# PiModulos_-_Rams_Head.net
KiCad netlist of a schematic drawn in Altium Designer
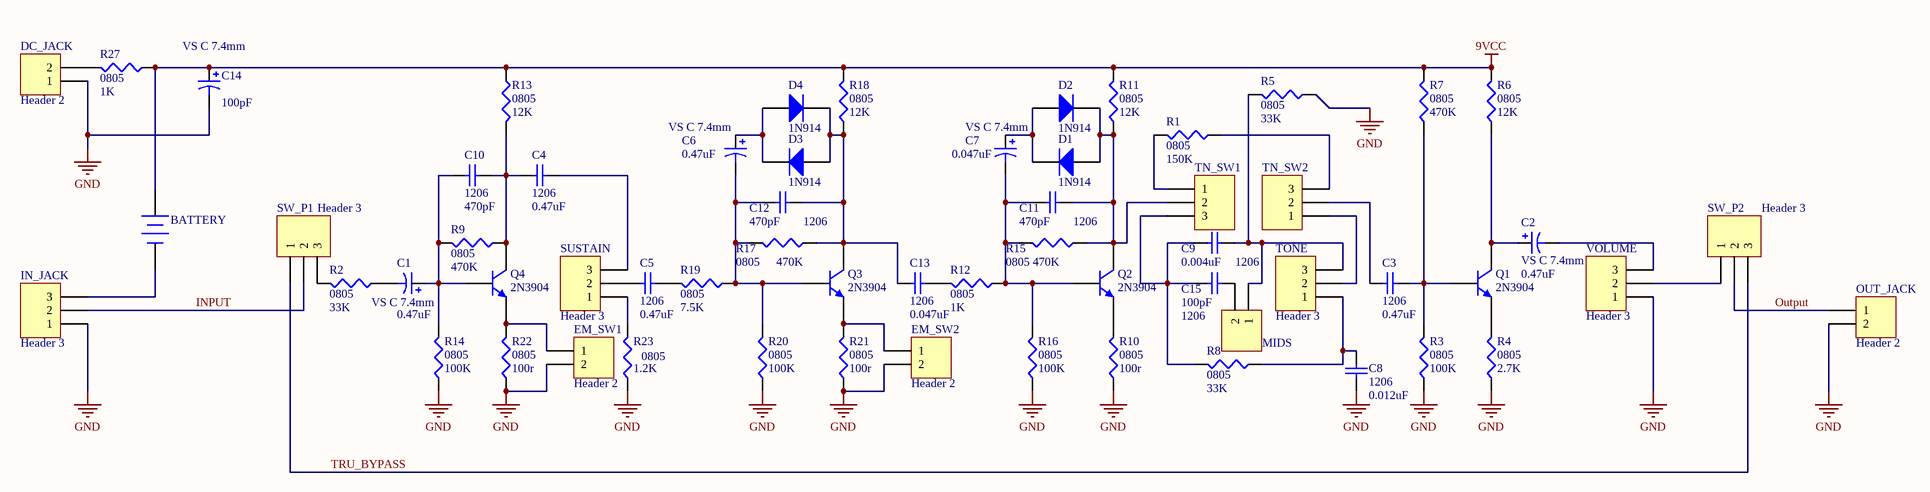
[diagram p0: PiModulos - Rams Head.SchDoc]

(export (version "E")
  (design (tool "Eeschema 10.0.6"))
  (components
    (comp (ref "BATTERY")
      (value "Battery")
      (footprint "BAT-2")
      (description "Multicell Battery")
      (fields (field (name "PUBLISHER") "Altium Limited"))
      (libsource (lib "Miscellaneous Devices") (part "Battery"))
    )
    (comp (ref "C1")
      (value "VS C 7.4mm")
      (footprint "Panasonic VS C")
      (description "Polarized Capacitor (Radial)")
      (fields (field (name "ALTIUM_VALUE") "0.47uF") (field (name "PUBLISHER") "Altium Limited"))
      (libsource (lib "Miscellaneous Devices") (part "Cap Pol1"))
    )
    (comp (ref "C2")
      (value "VS C 7.4mm")
      (footprint "Panasonic VS C")
      (description "Polarized Capacitor (Radial)")
      (fields (field (name "ALTIUM_VALUE") "0.47uF") (field (name "PUBLISHER") "Altium Limited"))
      (libsource (lib "Miscellaneous Devices") (part "Cap Pol1"))
    )
    (comp (ref "C3")
      (value "1206")
      (footprint "C1206")
      (description "Capacitor (Semiconductor SIM Model)")
      (fields (field (name "ALTIUM_VALUE") "0.47uF") (field (name "PUBLISHER") "Altium Limited"))
      (libsource (lib "Miscellaneous Devices") (part "Cap Semi"))
    )
    (comp (ref "C4")
      (value "1206")
      (footprint "C1206")
      (description "Capacitor (Semiconductor SIM Model)")
      (fields (field (name "ALTIUM_VALUE") "0.47uF") (field (name "PUBLISHER") "Altium Limited"))
      (libsource (lib "Miscellaneous Devices") (part "Cap Semi"))
    )
    (comp (ref "C5")
      (value "1206")
      (footprint "C1206")
      (description "Capacitor (Semiconductor SIM Model)")
      (fields (field (name "ALTIUM_VALUE") "0.47uF") (field (name "PUBLISHER") "Altium Limited"))
      (libsource (lib "Miscellaneous Devices") (part "Cap Semi"))
    )
    (comp (ref "C6")
      (value "VS C 7.4mm")
      (footprint "Panasonic VS C")
      (description "Polarized Capacitor (Radial)")
      (fields (field (name "ALTIUM_VALUE") "0.47uF") (field (name "PUBLISHER") "Altium Limited"))
      (libsource (lib "Miscellaneous Devices") (part "Cap Pol1"))
    )
    (comp (ref "C7")
      (value "VS C 7.4mm")
      (footprint "Panasonic VS C")
      (description "Polarized Capacitor (Radial)")
      (fields (field (name "ALTIUM_VALUE") "0.047uF") (field (name "PUBLISHER") "Altium Limited"))
      (libsource (lib "Miscellaneous Devices") (part "Cap Pol1"))
    )
    (comp (ref "C8")
      (value "1206")
      (footprint "C1206")
      (description "Capacitor (Semiconductor SIM Model)")
      (fields (field (name "ALTIUM_VALUE") "0.012uF") (field (name "PUBLISHER") "Altium Limited"))
      (libsource (lib "Miscellaneous Devices") (part "Cap Semi"))
    )
    (comp (ref "C9")
      (value "1206")
      (footprint "C1206")
      (description "Capacitor (Semiconductor SIM Model)")
      (fields (field (name "ALTIUM_VALUE") "0.004uF") (field (name "PUBLISHER") "Altium Limited"))
      (libsource (lib "Miscellaneous Devices") (part "Cap Semi"))
    )
    (comp (ref "C10")
      (value "1206")
      (footprint "C1206")
      (description "Capacitor (Semiconductor SIM Model)")
      (fields (field (name "ALTIUM_VALUE") "470pF") (field (name "PUBLISHER") "Altium Limited"))
      (libsource (lib "Miscellaneous Devices") (part "Cap Semi"))
    )
    (comp (ref "C11")
      (value "1206")
      (footprint "C1206")
      (description "Capacitor (Semiconductor SIM Model)")
      (fields (field (name "ALTIUM_VALUE") "470pF") (field (name "PUBLISHER") "Altium Limited"))
      (libsource (lib "Miscellaneous Devices") (part "Cap Semi"))
    )
    (comp (ref "C12")
      (value "1206")
      (footprint "C1206")
      (description "Capacitor (Semiconductor SIM Model)")
      (fields (field (name "ALTIUM_VALUE") "470pF") (field (name "PUBLISHER") "Altium Limited"))
      (libsource (lib "Miscellaneous Devices") (part "Cap Semi"))
    )
    (comp (ref "C13")
      (value "1206")
      (footprint "C1206")
      (description "Capacitor (Semiconductor SIM Model)")
      (fields (field (name "ALTIUM_VALUE") "0.047uF") (field (name "PUBLISHER") "Altium Limited"))
      (libsource (lib "Miscellaneous Devices") (part "Cap Semi"))
    )
    (comp (ref "C14")
      (value "VS C 7.4mm")
      (footprint "Panasonic VS C")
      (description "Polarized Capacitor (Radial)")
      (fields (field (name "ALTIUM_VALUE") "100pF") (field (name "PUBLISHER") "Altium Limited"))
      (libsource (lib "Miscellaneous Devices") (part "Cap Pol1"))
    )
    (comp (ref "C15")
      (value "1206")
      (footprint "C1206")
      (description "Capacitor (Semiconductor SIM Model)")
      (fields (field (name "ALTIUM_VALUE") "100pF") (field (name "PUBLISHER") "Altium Limited"))
      (libsource (lib "Miscellaneous Devices") (part "Cap Semi"))
    )
    (comp (ref "D1")
      (value "1N914")
      (footprint "DO-35")
      (description "High Conductance Fast Diode")
      (fields (field (name "PUBLISHER") "Altium Limited"))
      (libsource (lib "Miscellaneous Devices") (part "Diode 1N914"))
    )
    (comp (ref "D2")
      (value "1N914")
      (footprint "DO-35")
      (description "High Conductance Fast Diode")
      (fields (field (name "PUBLISHER") "Altium Limited"))
      (libsource (lib "Miscellaneous Devices") (part "Diode 1N914"))
    )
    (comp (ref "D3")
      (value "1N914")
      (footprint "DO-35")
      (description "High Conductance Fast Diode")
      (fields (field (name "PUBLISHER") "Altium Limited"))
      (libsource (lib "Miscellaneous Devices") (part "Diode 1N914"))
    )
    (comp (ref "D4")
      (value "1N914")
      (footprint "DO-35")
      (description "High Conductance Fast Diode")
      (fields (field (name "PUBLISHER") "Altium Limited"))
      (libsource (lib "Miscellaneous Devices") (part "Diode 1N914"))
    )
    (comp (ref "DC_JACK")
      (value "Header 2")
      (footprint "HDR1X2")
      (description "Header, 2-Pin")
      (fields (field (name "PUBLISHER") "Altium Limited"))
      (libsource (lib "") (part "Header 2_2"))
    )
    (comp (ref "EM_SW1")
      (value "Header 2")
      (footprint "HDR1X2")
      (description "Header, 2-Pin")
      (fields (field (name "PUBLISHER") "Altium Limited"))
      (libsource (lib "Miscellaneous Connectors") (part "Header 2"))
    )
    (comp (ref "EM_SW2")
      (value "Header 2")
      (footprint "HDR1X2")
      (description "Header, 2-Pin")
      (fields (field (name "PUBLISHER") "Altium Limited"))
      (libsource (lib "Miscellaneous Connectors") (part "Header 2"))
    )
    (comp (ref "IN_JACK")
      (value "Header 3")
      (footprint "HDR1X3")
      (description "Header, 3-Pin")
      (fields (field (name "PUBLISHER") "Altium Limited"))
      (libsource (lib "Miscellaneous Connectors") (part "Header 3"))
    )
    (comp (ref "MIDS")
      (value "Header 2")
      (footprint "HDR1X2")
      (description "Header, 2-Pin")
      (fields (field (name "PUBLISHER") "Altium Limited"))
      (libsource (lib "") (part "Header 2_1"))
    )
    (comp (ref "OUT_JACK")
      (value "Header 2")
      (footprint "HDR1X2")
      (description "Header, 2-Pin")
      (fields (field (name "PUBLISHER") "Altium Limited"))
      (libsource (lib "Miscellaneous Connectors") (part "Header 2"))
    )
    (comp (ref "Q1")
      (value "2N3904")
      (footprint "TO-92A")
      (description "NPN General Purpose Amplifier")
      (fields (field (name "PUBLISHER") "Altium Limited"))
      (libsource (lib "Miscellaneous Devices") (part "2N3904"))
    )
    (comp (ref "Q2")
      (value "2N3904")
      (footprint "TO-92A")
      (description "NPN General Purpose Amplifier")
      (fields (field (name "PUBLISHER") "Altium Limited"))
      (libsource (lib "Miscellaneous Devices") (part "2N3904"))
    )
    (comp (ref "Q3")
      (value "2N3904")
      (footprint "TO-92A")
      (description "NPN General Purpose Amplifier")
      (fields (field (name "PUBLISHER") "Altium Limited"))
      (libsource (lib "Miscellaneous Devices") (part "2N3904"))
    )
    (comp (ref "Q4")
      (value "2N3904")
      (footprint "TO-92A")
      (description "NPN General Purpose Amplifier")
      (fields (field (name "PUBLISHER") "Altium Limited"))
      (libsource (lib "Miscellaneous Devices") (part "2N3904"))
    )
    (comp (ref "R1")
      (value "0805")
      (footprint "SM 0805 - gap trimmed")
      (description "Resistor")
      (fields (field (name "ALTIUM_VALUE") "150K") (field (name "PUBLISHER") "Altium Limited"))
      (libsource (lib "Miscellaneous Devices") (part "Res3"))
    )
    (comp (ref "R2")
      (value "0805")
      (footprint "SM 0805 - gap trimmed")
      (description "Resistor")
      (fields (field (name "ALTIUM_VALUE") "33K") (field (name "PUBLISHER") "Altium Limited"))
      (libsource (lib "Miscellaneous Devices") (part "Res3"))
    )
    (comp (ref "R3")
      (value "0805")
      (footprint "SM 0805 - gap trimmed")
      (description "Resistor")
      (fields (field (name "ALTIUM_VALUE") "100K") (field (name "PUBLISHER") "Altium Limited"))
      (libsource (lib "Miscellaneous Devices") (part "Res3"))
    )
    (comp (ref "R4")
      (value "0805")
      (footprint "SM 0805 - gap trimmed")
      (description "Resistor")
      (fields (field (name "ALTIUM_VALUE") "2.7K") (field (name "PUBLISHER") "Altium Limited"))
      (libsource (lib "Miscellaneous Devices") (part "Res3"))
    )
    (comp (ref "R5")
      (value "0805")
      (footprint "SM 0805 - gap trimmed")
      (description "Resistor")
      (fields (field (name "ALTIUM_VALUE") "33K") (field (name "PUBLISHER") "Altium Limited"))
      (libsource (lib "Miscellaneous Devices") (part "Res3"))
    )
    (comp (ref "R6")
      (value "0805")
      (footprint "SM 0805 - gap trimmed")
      (description "Resistor")
      (fields (field (name "ALTIUM_VALUE") "12K") (field (name "PUBLISHER") "Altium Limited"))
      (libsource (lib "Miscellaneous Devices") (part "Res3"))
    )
    (comp (ref "R7")
      (value "0805")
      (footprint "SM 0805 - gap trimmed")
      (description "Resistor")
      (fields (field (name "ALTIUM_VALUE") "470K") (field (name "PUBLISHER") "Altium Limited"))
      (libsource (lib "Miscellaneous Devices") (part "Res3"))
    )
    (comp (ref "R8")
      (value "0805")
      (footprint "SM 0805 - gap trimmed")
      (description "Resistor")
      (fields (field (name "ALTIUM_VALUE") "33K") (field (name "PUBLISHER") "Altium Limited"))
      (libsource (lib "Miscellaneous Devices") (part "Res3"))
    )
    (comp (ref "R9")
      (value "0805")
      (footprint "SM 0805 - gap trimmed")
      (description "Resistor")
      (fields (field (name "ALTIUM_VALUE") "470K") (field (name "PUBLISHER") "Altium Limited"))
      (libsource (lib "Miscellaneous Devices") (part "Res3"))
    )
    (comp (ref "R10")
      (value "0805")
      (footprint "SM 0805 - gap trimmed")
      (description "Resistor")
      (fields (field (name "ALTIUM_VALUE") "100r") (field (name "PUBLISHER") "Altium Limited"))
      (libsource (lib "Miscellaneous Devices") (part "Res3"))
    )
    (comp (ref "R11")
      (value "0805")
      (footprint "SM 0805 - gap trimmed")
      (description "Resistor")
      (fields (field (name "ALTIUM_VALUE") "12K") (field (name "PUBLISHER") "Altium Limited"))
      (libsource (lib "Miscellaneous Devices") (part "Res3"))
    )
    (comp (ref "R12")
      (value "0805")
      (footprint "SM 0805 - gap trimmed")
      (description "Resistor")
      (fields (field (name "ALTIUM_VALUE") "1K") (field (name "PUBLISHER") "Altium Limited"))
      (libsource (lib "Miscellaneous Devices") (part "Res3"))
    )
    (comp (ref "R13")
      (value "0805")
      (footprint "SM 0805 - gap trimmed")
      (description "Resistor")
      (fields (field (name "ALTIUM_VALUE") "12K") (field (name "PUBLISHER") "Altium Limited"))
      (libsource (lib "Miscellaneous Devices") (part "Res3"))
    )
    (comp (ref "R14")
      (value "0805")
      (footprint "SM 0805 - gap trimmed")
      (description "Resistor")
      (fields (field (name "ALTIUM_VALUE") "100K") (field (name "PUBLISHER") "Altium Limited"))
      (libsource (lib "Miscellaneous Devices") (part "Res3"))
    )
    (comp (ref "R15")
      (value "0805")
      (footprint "SM 0805 - gap trimmed")
      (description "Resistor")
      (fields (field (name "ALTIUM_VALUE") "470K") (field (name "PUBLISHER") "Altium Limited"))
      (libsource (lib "Miscellaneous Devices") (part "Res3"))
    )
    (comp (ref "R16")
      (value "0805")
      (footprint "SM 0805 - gap trimmed")
      (description "Resistor")
      (fields (field (name "ALTIUM_VALUE") "100K") (field (name "PUBLISHER") "Altium Limited"))
      (libsource (lib "Miscellaneous Devices") (part "Res3"))
    )
    (comp (ref "R17")
      (value "0805")
      (footprint "SM 0805 - gap trimmed")
      (description "Resistor")
      (fields (field (name "ALTIUM_VALUE") "470K") (field (name "PUBLISHER") "Altium Limited"))
      (libsource (lib "Miscellaneous Devices") (part "Res3"))
    )
    (comp (ref "R18")
      (value "0805")
      (footprint "SM 0805 - gap trimmed")
      (description "Resistor")
      (fields (field (name "ALTIUM_VALUE") "12K") (field (name "PUBLISHER") "Altium Limited"))
      (libsource (lib "Miscellaneous Devices") (part "Res3"))
    )
    (comp (ref "R19")
      (value "0805")
      (footprint "SM 0805 - gap trimmed")
      (description "Resistor")
      (fields (field (name "ALTIUM_VALUE") "7.5K") (field (name "PUBLISHER") "Altium Limited"))
      (libsource (lib "Miscellaneous Devices") (part "Res3"))
    )
    (comp (ref "R20")
      (value "0805")
      (footprint "SM 0805 - gap trimmed")
      (description "Resistor")
      (fields (field (name "ALTIUM_VALUE") "100K") (field (name "PUBLISHER") "Altium Limited"))
      (libsource (lib "Miscellaneous Devices") (part "Res3"))
    )
    (comp (ref "R21")
      (value "0805")
      (footprint "SM 0805 - gap trimmed")
      (description "Resistor")
      (fields (field (name "ALTIUM_VALUE") "100r") (field (name "PUBLISHER") "Altium Limited"))
      (libsource (lib "Miscellaneous Devices") (part "Res3"))
    )
    (comp (ref "R22")
      (value "0805")
      (footprint "SM 0805 - gap trimmed")
      (description "Resistor")
      (fields (field (name "ALTIUM_VALUE") "100r") (field (name "PUBLISHER") "Altium Limited"))
      (libsource (lib "Miscellaneous Devices") (part "Res3"))
    )
    (comp (ref "R23")
      (value "0805")
      (footprint "SM 0805 - gap trimmed")
      (description "Resistor")
      (fields (field (name "ALTIUM_VALUE") "1.2K") (field (name "PUBLISHER") "Altium Limited"))
      (libsource (lib "Miscellaneous Devices") (part "Res3"))
    )
    (comp (ref "R27")
      (value "0805")
      (footprint "SM 0805 - gap trimmed")
      (description "Resistor")
      (fields (field (name "ALTIUM_VALUE") "1K") (field (name "PUBLISHER") "Altium Limited"))
      (libsource (lib "Miscellaneous Devices") (part "Res3"))
    )
    (comp (ref "SUSTAIN")
      (value "Header 3")
      (footprint "HDR1X3")
      (description "Header, 3-Pin")
      (fields (field (name "PUBLISHER") "Altium Limited"))
      (libsource (lib "Miscellaneous Connectors") (part "Header 3"))
    )
    (comp (ref "SW_P1")
      (value "Header 3")
      (footprint "HDR1X3")
      (description "Header, 3-Pin")
      (fields (field (name "PUBLISHER") "Altium Limited"))
      (libsource (lib "") (part "Header 3_1"))
    )
    (comp (ref "SW_P2")
      (value "Header 3")
      (footprint "HDR1X3")
      (description "Header, 3-Pin")
      (fields (field (name "PUBLISHER") "Altium Limited"))
      (libsource (lib "") (part "Header 3_1"))
    )
    (comp (ref "TN_SW1")
      (value "Header 3")
      (footprint "HDR1X3")
      (description "Header, 3-Pin")
      (fields (field (name "PUBLISHER") "Altium Limited"))
      (libsource (lib "") (part "Header 3_2"))
    )
    (comp (ref "TN_SW2")
      (value "Header 3")
      (footprint "HDR1X3")
      (description "Header, 3-Pin")
      (fields (field (name "PUBLISHER") "Altium Limited"))
      (libsource (lib "Miscellaneous Connectors") (part "Header 3"))
    )
    (comp (ref "TONE")
      (value "Header 3")
      (footprint "HDR1X3")
      (description "Header, 3-Pin")
      (fields (field (name "PUBLISHER") "Altium Limited"))
      (libsource (lib "Miscellaneous Connectors") (part "Header 3"))
    )
    (comp (ref "VOLUME")
      (value "Header 3")
      (footprint "HDR1X3")
      (description "Header, 3-Pin")
      (fields (field (name "PUBLISHER") "Altium Limited"))
      (libsource (lib "Miscellaneous Connectors") (part "Header 3"))
    )
  )
  (nets
    (net (code "1") (name "/INPUT") (class "Default")
      (node (ref "IN_JACK") (pin "2") (pinfunction "2_2") (pintype "passive"))
      (node (ref "SW_P1") (pin "2") (pinfunction "2_2") (pintype "passive"))
    )
    (net (code "2") (name "/Output") (class "Default")
      (node (ref "OUT_JACK") (pin "1") (pinfunction "1_1") (pintype "passive"))
      (node (ref "SW_P2") (pin "2") (pinfunction "2_2") (pintype "passive"))
    )
    (net (code "3") (name "/TRU_BYPASS") (class "Default")
      (node (ref "SW_P1") (pin "1") (pinfunction "1_1") (pintype "passive"))
      (node (ref "SW_P2") (pin "3") (pinfunction "3_3") (pintype "passive"))
    )
    (net (code "4") (name "9VCC") (class "Default")
      (node (ref "BATTERY") (pin "1") (pinfunction "+_1") (pintype "passive"))
      (node (ref "C14") (pin "1") (pinfunction "1_1") (pintype "passive"))
      (node (ref "R11") (pin "2") (pinfunction "2_2") (pintype "passive"))
      (node (ref "R13") (pin "1") (pinfunction "1_1") (pintype "passive"))
      (node (ref "R18") (pin "2") (pinfunction "2_2") (pintype "passive"))
      (node (ref "R27") (pin "1") (pinfunction "1_1") (pintype "passive"))
      (node (ref "R6") (pin "2") (pinfunction "2_2") (pintype "passive"))
      (node (ref "R7") (pin "2") (pinfunction "2_2") (pintype "passive"))
    )
    (net (code "5") (name "GND") (class "Default")
      (node (ref "C14") (pin "2") (pinfunction "2_2") (pintype "passive"))
      (node (ref "C8") (pin "1") (pinfunction "1_1") (pintype "passive"))
      (node (ref "DC_JACK") (pin "1") (pinfunction "1_1") (pintype "passive"))
      (node (ref "EM_SW1") (pin "2") (pinfunction "2_2") (pintype "passive"))
      (node (ref "EM_SW2") (pin "2") (pinfunction "2_2") (pintype "passive"))
      (node (ref "IN_JACK") (pin "1") (pinfunction "1_1") (pintype "passive"))
      (node (ref "OUT_JACK") (pin "2") (pinfunction "2_2") (pintype "passive"))
      (node (ref "R10") (pin "1") (pinfunction "1_1") (pintype "passive"))
      (node (ref "R14") (pin "1") (pinfunction "1_1") (pintype "passive"))
      (node (ref "R16") (pin "1") (pinfunction "1_1") (pintype "passive"))
      (node (ref "R20") (pin "1") (pinfunction "1_1") (pintype "passive"))
      (node (ref "R21") (pin "1") (pinfunction "1_1") (pintype "passive"))
      (node (ref "R22") (pin "1") (pinfunction "1_1") (pintype "passive"))
      (node (ref "R23") (pin "1") (pinfunction "1_1") (pintype "passive"))
      (node (ref "R3") (pin "1") (pinfunction "1_1") (pintype "passive"))
      (node (ref "R4") (pin "1") (pinfunction "1_1") (pintype "passive"))
      (node (ref "R5") (pin "1") (pinfunction "1_1") (pintype "passive"))
      (node (ref "VOLUME") (pin "1") (pinfunction "1_1") (pintype "passive"))
    )
    (net (code "6") (name "Net-(BATTERY--)") (class "Default")
      (node (ref "BATTERY") (pin "2") (pinfunction "-_2") (pintype "passive"))
      (node (ref "IN_JACK") (pin "3") (pinfunction "3_3") (pintype "passive"))
    )
    (net (code "7") (name "Net-(C1-Pad2)") (class "Default")
      (node (ref "C1") (pin "2") (pinfunction "2_2") (pintype "passive"))
      (node (ref "R2") (pin "1") (pinfunction "1_1") (pintype "passive"))
    )
    (net (code "8") (name "Net-(C2-Pad2)") (class "Default")
      (node (ref "C2") (pin "2") (pinfunction "2_2") (pintype "passive"))
      (node (ref "VOLUME") (pin "3") (pinfunction "3_3") (pintype "passive"))
    )
    (net (code "9") (name "Net-(C3-Pad1)") (class "Default")
      (node (ref "C3") (pin "1") (pinfunction "1_1") (pintype "passive"))
      (node (ref "TN_SW2") (pin "2") (pinfunction "2_2") (pintype "passive"))
    )
    (net (code "10") (name "Net-(C4-Pad2)") (class "Default")
      (node (ref "C4") (pin "2") (pinfunction "2_2") (pintype "passive"))
      (node (ref "SUSTAIN") (pin "3") (pinfunction "3_3") (pintype "passive"))
    )
    (net (code "11") (name "Net-(C5-Pad1)") (class "Default")
      (node (ref "C5") (pin "1") (pinfunction "1_1") (pintype "passive"))
      (node (ref "SUSTAIN") (pin "2") (pinfunction "2_2") (pintype "passive"))
    )
    (net (code "12") (name "Net-(C5-Pad2)") (class "Default")
      (node (ref "C5") (pin "2") (pinfunction "2_2") (pintype "passive"))
      (node (ref "R19") (pin "2") (pinfunction "2_2") (pintype "passive"))
    )
    (net (code "13") (name "Net-(C8-Pad2)") (class "Default")
      (node (ref "C8") (pin "2") (pinfunction "2_2") (pintype "passive"))
      (node (ref "R8") (pin "1") (pinfunction "1_1") (pintype "passive"))
      (node (ref "TONE") (pin "1") (pinfunction "1_1") (pintype "passive"))
    )
    (net (code "14") (name "Net-(C9-Pad2)") (class "Default")
      (node (ref "C9") (pin "2") (pinfunction "2_2") (pintype "passive"))
      (node (ref "MIDS") (pin "1") (pinfunction "1_1") (pintype "passive"))
      (node (ref "R5") (pin "2") (pinfunction "2_2") (pintype "passive"))
      (node (ref "TONE") (pin "3") (pinfunction "3_3") (pintype "passive"))
    )
    (net (code "15") (name "Net-(C13-Pad2)") (class "Default")
      (node (ref "C13") (pin "2") (pinfunction "2_2") (pintype "passive"))
      (node (ref "R12") (pin "2") (pinfunction "2_2") (pintype "passive"))
    )
    (net (code "16") (name "Net-(C15-Pad1)") (class "Default")
      (node (ref "C15") (pin "1") (pinfunction "1_1") (pintype "passive"))
      (node (ref "C9") (pin "1") (pinfunction "1_1") (pintype "passive"))
      (node (ref "R8") (pin "2") (pinfunction "2_2") (pintype "passive"))
      (node (ref "TN_SW1") (pin "3") (pinfunction "3_3") (pintype "passive"))
    )
    (net (code "17") (name "Net-(C15-Pad2)") (class "Default")
      (node (ref "C15") (pin "2") (pinfunction "2_2") (pintype "passive"))
      (node (ref "MIDS") (pin "2") (pinfunction "2_2") (pintype "passive"))
    )
    (net (code "18") (name "Net-(D1-A)") (class "Default")
      (node (ref "C11") (pin "2") (pinfunction "2_2") (pintype "passive"))
      (node (ref "D1") (pin "1") (pinfunction "A_1") (pintype "passive"))
      (node (ref "D2") (pin "2") (pinfunction "K_2") (pintype "passive"))
      (node (ref "Q2") (pin "3") (pinfunction "C_3") (pintype "passive"))
      (node (ref "R11") (pin "1") (pinfunction "1_1") (pintype "passive"))
      (node (ref "R15") (pin "1") (pinfunction "1_1") (pintype "passive"))
      (node (ref "TN_SW1") (pin "2") (pinfunction "2_2") (pintype "passive"))
    )
    (net (code "19") (name "Net-(D1-K)") (class "Default")
      (node (ref "C7") (pin "1") (pinfunction "1_1") (pintype "passive"))
      (node (ref "D1") (pin "2") (pinfunction "K_2") (pintype "passive"))
      (node (ref "D2") (pin "1") (pinfunction "A_1") (pintype "passive"))
    )
    (net (code "20") (name "Net-(D3-A)") (class "Default")
      (node (ref "C12") (pin "2") (pinfunction "2_2") (pintype "passive"))
      (node (ref "C13") (pin "1") (pinfunction "1_1") (pintype "passive"))
      (node (ref "D3") (pin "1") (pinfunction "A_1") (pintype "passive"))
      (node (ref "D4") (pin "2") (pinfunction "K_2") (pintype "passive"))
      (node (ref "Q3") (pin "3") (pinfunction "C_3") (pintype "passive"))
      (node (ref "R17") (pin "1") (pinfunction "1_1") (pintype "passive"))
      (node (ref "R18") (pin "1") (pinfunction "1_1") (pintype "passive"))
    )
    (net (code "21") (name "Net-(D3-K)") (class "Default")
      (node (ref "C6") (pin "1") (pinfunction "1_1") (pintype "passive"))
      (node (ref "D3") (pin "2") (pinfunction "K_2") (pintype "passive"))
      (node (ref "D4") (pin "1") (pinfunction "A_1") (pintype "passive"))
    )
    (net (code "22") (name "Net-(DC_JACK-Pad2)") (class "Default")
      (node (ref "DC_JACK") (pin "2") (pinfunction "2_2") (pintype "passive"))
      (node (ref "R27") (pin "2") (pinfunction "2_2") (pintype "passive"))
    )
    (net (code "23") (name "Net-(Q1-B)") (class "Default")
      (node (ref "C3") (pin "2") (pinfunction "2_2") (pintype "passive"))
      (node (ref "Q1") (pin "2") (pinfunction "B_2") (pintype "passive"))
      (node (ref "R3") (pin "2") (pinfunction "2_2") (pintype "passive"))
      (node (ref "R7") (pin "1") (pinfunction "1_1") (pintype "passive"))
    )
    (net (code "24") (name "Net-(Q1-C)") (class "Default")
      (node (ref "C2") (pin "1") (pinfunction "1_1") (pintype "passive"))
      (node (ref "Q1") (pin "3") (pinfunction "C_3") (pintype "passive"))
      (node (ref "R6") (pin "1") (pinfunction "1_1") (pintype "passive"))
    )
    (net (code "25") (name "Net-(Q1-E)") (class "Default")
      (node (ref "Q1") (pin "1") (pinfunction "E_1") (pintype "passive"))
      (node (ref "R4") (pin "2") (pinfunction "2_2") (pintype "passive"))
    )
    (net (code "26") (name "Net-(Q2-B)") (class "Default")
      (node (ref "C11") (pin "1") (pinfunction "1_1") (pintype "passive"))
      (node (ref "C7") (pin "2") (pinfunction "2_2") (pintype "passive"))
      (node (ref "Q2") (pin "2") (pinfunction "B_2") (pintype "passive"))
      (node (ref "R12") (pin "1") (pinfunction "1_1") (pintype "passive"))
      (node (ref "R15") (pin "2") (pinfunction "2_2") (pintype "passive"))
      (node (ref "R16") (pin "2") (pinfunction "2_2") (pintype "passive"))
    )
    (net (code "27") (name "Net-(Q2-E)") (class "Default")
      (node (ref "Q2") (pin "1") (pinfunction "E_1") (pintype "passive"))
      (node (ref "R10") (pin "2") (pinfunction "2_2") (pintype "passive"))
    )
    (net (code "28") (name "Net-(Q3-B)") (class "Default")
      (node (ref "C12") (pin "1") (pinfunction "1_1") (pintype "passive"))
      (node (ref "C6") (pin "2") (pinfunction "2_2") (pintype "passive"))
      (node (ref "Q3") (pin "2") (pinfunction "B_2") (pintype "passive"))
      (node (ref "R17") (pin "2") (pinfunction "2_2") (pintype "passive"))
      (node (ref "R19") (pin "1") (pinfunction "1_1") (pintype "passive"))
      (node (ref "R20") (pin "2") (pinfunction "2_2") (pintype "passive"))
    )
    (net (code "29") (name "Net-(Q3-E)") (class "Default")
      (node (ref "EM_SW2") (pin "1") (pinfunction "1_1") (pintype "passive"))
      (node (ref "Q3") (pin "1") (pinfunction "E_1") (pintype "passive"))
      (node (ref "R21") (pin "2") (pinfunction "2_2") (pintype "passive"))
    )
    (net (code "30") (name "Net-(Q4-B)") (class "Default")
      (node (ref "C1") (pin "1") (pinfunction "1_1") (pintype "passive"))
      (node (ref "C10") (pin "1") (pinfunction "1_1") (pintype "passive"))
      (node (ref "Q4") (pin "2") (pinfunction "B_2") (pintype "passive"))
      (node (ref "R14") (pin "2") (pinfunction "2_2") (pintype "passive"))
      (node (ref "R9") (pin "2") (pinfunction "2_2") (pintype "passive"))
    )
    (net (code "31") (name "Net-(Q4-C)") (class "Default")
      (node (ref "C10") (pin "2") (pinfunction "2_2") (pintype "passive"))
      (node (ref "C4") (pin "1") (pinfunction "1_1") (pintype "passive"))
      (node (ref "Q4") (pin "3") (pinfunction "C_3") (pintype "passive"))
      (node (ref "R13") (pin "2") (pinfunction "2_2") (pintype "passive"))
      (node (ref "R9") (pin "1") (pinfunction "1_1") (pintype "passive"))
    )
    (net (code "32") (name "Net-(Q4-E)") (class "Default")
      (node (ref "EM_SW1") (pin "1") (pinfunction "1_1") (pintype "passive"))
      (node (ref "Q4") (pin "1") (pinfunction "E_1") (pintype "passive"))
      (node (ref "R22") (pin "2") (pinfunction "2_2") (pintype "passive"))
    )
    (net (code "33") (name "Net-(R1-Pad1)") (class "Default")
      (node (ref "R1") (pin "1") (pinfunction "1_1") (pintype "passive"))
      (node (ref "TN_SW2") (pin "3") (pinfunction "3_3") (pintype "passive"))
    )
    (net (code "34") (name "Net-(R1-Pad2)") (class "Default")
      (node (ref "R1") (pin "2") (pinfunction "2_2") (pintype "passive"))
      (node (ref "TN_SW1") (pin "1") (pinfunction "1_1") (pintype "passive"))
    )
    (net (code "35") (name "Net-(R2-Pad2)") (class "Default")
      (node (ref "R2") (pin "2") (pinfunction "2_2") (pintype "passive"))
      (node (ref "SW_P1") (pin "3") (pinfunction "3_3") (pintype "passive"))
    )
    (net (code "36") (name "Net-(R23-Pad2)") (class "Default")
      (node (ref "R23") (pin "2") (pinfunction "2_2") (pintype "passive"))
      (node (ref "SUSTAIN") (pin "1") (pinfunction "1_1") (pintype "passive"))
    )
    (net (code "37") (name "Net-(SW_P2-Pad1)") (class "Default")
      (node (ref "SW_P2") (pin "1") (pinfunction "1_1") (pintype "passive"))
      (node (ref "VOLUME") (pin "2") (pinfunction "2_2") (pintype "passive"))
    )
    (net (code "38") (name "Net-(TN_SW2-Pad1)") (class "Default")
      (node (ref "TN_SW2") (pin "1") (pinfunction "1_1") (pintype "passive"))
      (node (ref "TONE") (pin "2") (pinfunction "2_2") (pintype "passive"))
    )
  )
)
